# node_v2.net
KiCad netlist of a schematic drawn in EAGLE
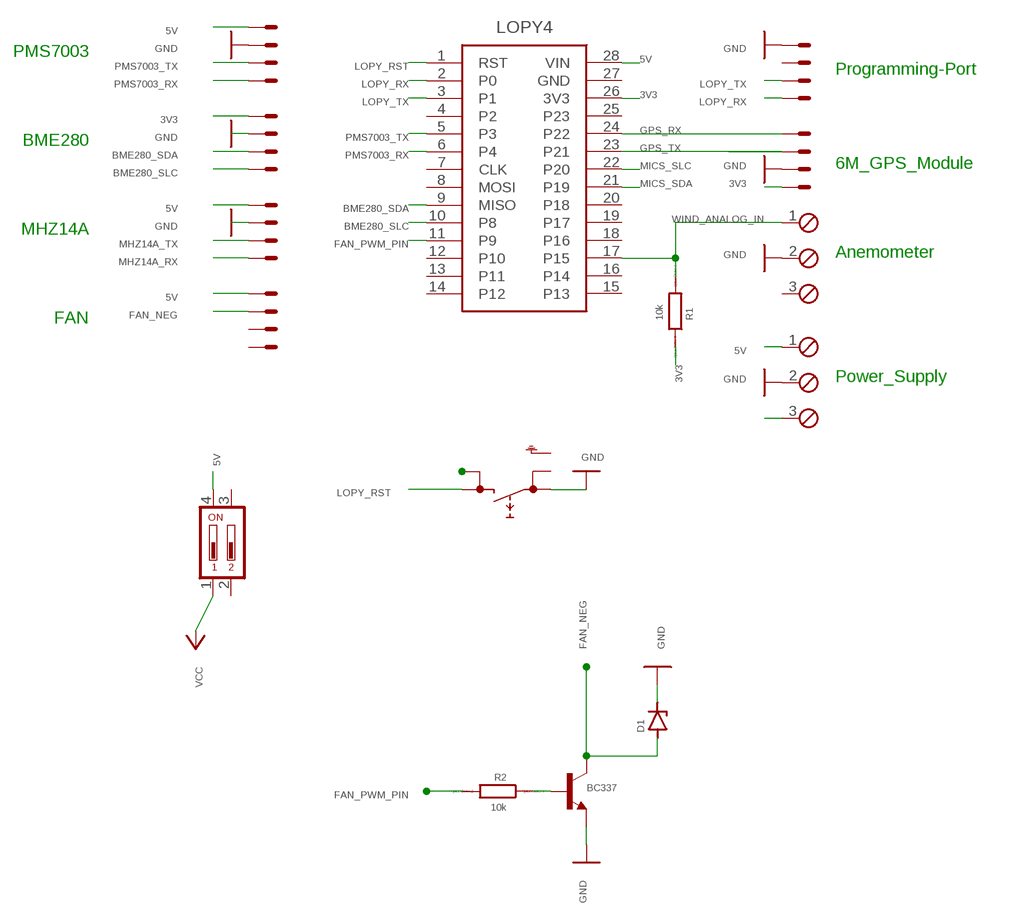
[diagram p0: schematic, sheet 1]

(export (version "E")
  (design (tool "Eeschema 10.0.6"))
  (components
    (comp (ref "D1")
      (value "1N821")
      (footprint "eagle-import:DO35Z10")
      (libsource (lib "eagle-import") (part "1N821"))
    )
    (comp (ref "IC1")
      (value "LOPY4")
      (footprint "eagle-import:LOPY4")
      (fields (field (name "MOUSER_PART_NUMBER") "365-LOPY4"))
      (libsource (lib "eagle-import") (part "LOPY4"))
    )
    (comp (ref "R1")
      (value "10k")
      (footprint "eagle-import:0207_10")
      (fields (field (name "SPICEMODEL") "12"))
      (libsource (lib "eagle-import") (part "R0207/10"))
    )
    (comp (ref "R2")
      (value "10k")
      (footprint "eagle-import:0207_10")
      (fields (field (name "SPICEMODEL") "12"))
      (libsource (lib "eagle-import") (part "R0207/10"))
    )
    (comp (ref "S1")
      (value "DA02")
      (footprint "eagle-import:DA-02")
      (libsource (lib "eagle-import") (part "DA02"))
    )
    (comp (ref "S2")
      (value "SKHMPSE010")
      (footprint "eagle-import:SKHMPXE010")
      (libsource (lib "eagle-import") (part "SKHMPE010S"))
    )
    (comp (ref "T1")
      (value "BC337")
      (footprint "eagle-import:TO92")
      (libsource (lib "eagle-import") (part "BC337"))
    )
    (comp (ref "X1")
      (value "22-23-2041")
      (footprint "eagle-import:22-23-2041")
      (fields (field (name "MF") "MOLEX"))
      (libsource (lib "eagle-import") (part "22-23-2041"))
    )
    (comp (ref "X4")
      (value "22-23-2041")
      (footprint "eagle-import:22-23-2041")
      (fields (field (name "MF") "MOLEX"))
      (libsource (lib "eagle-import") (part "22-23-2041"))
    )
    (comp (ref "X5")
      (value "MPT3")
      (footprint "eagle-import:3POL254")
      (libsource (lib "eagle-import") (part "MPT3"))
    )
    (comp (ref "X6")
      (value "MPT3")
      (footprint "eagle-import:3POL254")
      (libsource (lib "eagle-import") (part "MPT3"))
    )
    (comp (ref "X7")
      (value "22-23-2041")
      (footprint "eagle-import:22-23-2041")
      (fields (field (name "MF") "MOLEX"))
      (libsource (lib "eagle-import") (part "22-23-2041"))
    )
    (comp (ref "X8")
      (value "22-23-2041")
      (footprint "eagle-import:22-23-2041")
      (fields (field (name "MF") "MOLEX"))
      (libsource (lib "eagle-import") (part "22-23-2041"))
    )
    (comp (ref "X9")
      (value "22-23-2041")
      (footprint "eagle-import:22-23-2041")
      (fields (field (name "MF") "MOLEX"))
      (libsource (lib "eagle-import") (part "22-23-2041"))
    )
    (comp (ref "X10")
      (value "22-23-2041")
      (footprint "eagle-import:22-23-2041")
      (fields (field (name "MF") "MOLEX"))
      (libsource (lib "eagle-import") (part "22-23-2041"))
    )
  )
  (nets
    (net (code "1") (name "/3V3") (class "Default")
      (node (ref "IC1") (pin "26") (pinfunction "3V3_26") (pintype "bidirectional"))
      (node (ref "R1") (pin "1") (pinfunction "1_1") (pintype "passive"))
      (node (ref "X4") (pin "4") (pinfunction "S_4") (pintype "passive"))
      (node (ref "X8") (pin "1") (pinfunction "S_1") (pintype "passive"))
    )
    (net (code "2") (name "/5V") (class "Default")
      (node (ref "IC1") (pin "28") (pinfunction "VIN_28") (pintype "bidirectional"))
      (node (ref "S1") (pin "4") (pinfunction "4_4") (pintype "passive"))
      (node (ref "X10") (pin "1") (pinfunction "S_1") (pintype "passive"))
      (node (ref "X6") (pin "1") (pinfunction "1_1") (pintype "passive"))
      (node (ref "X7") (pin "1") (pinfunction "S_1") (pintype "passive"))
      (node (ref "X9") (pin "1") (pinfunction "S_1") (pintype "passive"))
    )
    (net (code "3") (name "/BME280_SDA") (class "Default")
      (node (ref "IC1") (pin "9") (pinfunction "MISO_9") (pintype "bidirectional"))
      (node (ref "X8") (pin "3") (pinfunction "S_3") (pintype "passive"))
    )
    (net (code "4") (name "/BME280_SLC") (class "Default")
      (node (ref "IC1") (pin "10") (pinfunction "P8_10") (pintype "bidirectional"))
      (node (ref "X8") (pin "4") (pinfunction "S_4") (pintype "passive"))
    )
    (net (code "5") (name "/FAN_NEG") (class "Default")
      (node (ref "D1") (pin "A") (pinfunction "A_A") (pintype "passive"))
      (node (ref "T1") (pin "3") (pinfunction "C_3") (pintype "passive"))
      (node (ref "X10") (pin "2") (pinfunction "S_2") (pintype "passive"))
    )
    (net (code "6") (name "/FAN_PWM_PIN") (class "Default")
      (node (ref "IC1") (pin "11") (pinfunction "P9_11") (pintype "bidirectional"))
      (node (ref "R2") (pin "2") (pinfunction "2_2") (pintype "passive"))
    )
    (net (code "7") (name "/GPS_RX") (class "Default")
      (node (ref "IC1") (pin "24") (pinfunction "P22_24") (pintype "bidirectional"))
      (node (ref "X4") (pin "1") (pinfunction "S_1") (pintype "passive"))
    )
    (net (code "8") (name "/GPS_TX") (class "Default")
      (node (ref "IC1") (pin "23") (pinfunction "P21_23") (pintype "bidirectional"))
      (node (ref "X4") (pin "2") (pinfunction "S_2") (pintype "passive"))
    )
    (net (code "9") (name "/LOPY_RST") (class "Default")
      (node (ref "IC1") (pin "1") (pinfunction "RST_1") (pintype "bidirectional"))
      (node (ref "S2") (pin "3") (pinfunction "2.1_3") (pintype "passive"))
    )
    (net (code "10") (name "/LOPY_RX") (class "Default")
      (node (ref "IC1") (pin "2") (pinfunction "P0_2") (pintype "bidirectional"))
    )
    (net (code "11") (name "/LOPY_TX") (class "Default")
      (node (ref "IC1") (pin "3") (pinfunction "P1_3") (pintype "bidirectional"))
    )
    (net (code "12") (name "/MHZ14A_RX") (class "Default")
      (node (ref "X9") (pin "4") (pinfunction "S_4") (pintype "passive"))
    )
    (net (code "13") (name "/MHZ14A_TX") (class "Default")
      (node (ref "X9") (pin "3") (pinfunction "S_3") (pintype "passive"))
    )
    (net (code "14") (name "/MICS_SDA") (class "Default")
      (node (ref "IC1") (pin "21") (pinfunction "P19_21") (pintype "bidirectional"))
    )
    (net (code "15") (name "/MICS_SLC") (class "Default")
      (node (ref "IC1") (pin "22") (pinfunction "P20_22") (pintype "bidirectional"))
    )
    (net (code "16") (name "/PMS7003_RX") (class "Default")
      (node (ref "IC1") (pin "6") (pinfunction "P4_6") (pintype "bidirectional"))
      (node (ref "X7") (pin "4") (pinfunction "S_4") (pintype "passive"))
    )
    (net (code "17") (name "/PMS7003_TX") (class "Default")
      (node (ref "IC1") (pin "5") (pinfunction "P3_5") (pintype "bidirectional"))
      (node (ref "X7") (pin "3") (pinfunction "S_3") (pintype "passive"))
    )
    (net (code "18") (name "/WIND_ANALOG_IN") (class "Default")
      (node (ref "IC1") (pin "17") (pinfunction "P15_17") (pintype "bidirectional"))
      (node (ref "R1") (pin "2") (pinfunction "2_2") (pintype "passive"))
      (node (ref "X5") (pin "1") (pinfunction "1_1") (pintype "passive"))
    )
    (net (code "19") (name "GND") (class "Default")
      (node (ref "D1") (pin "C") (pinfunction "C_C") (pintype "passive"))
      (node (ref "S2") (pin "1") (pinfunction "1.1_1") (pintype "passive"))
      (node (ref "T1") (pin "1") (pinfunction "E_1") (pintype "passive"))
      (node (ref "X1") (pin "1") (pinfunction "S_1") (pintype "passive"))
      (node (ref "X4") (pin "3") (pinfunction "S_3") (pintype "passive"))
      (node (ref "X5") (pin "2") (pinfunction "1_2") (pintype "passive"))
      (node (ref "X6") (pin "2") (pinfunction "1_2") (pintype "passive"))
      (node (ref "X7") (pin "2") (pinfunction "S_2") (pintype "passive"))
      (node (ref "X8") (pin "2") (pinfunction "S_2") (pintype "passive"))
      (node (ref "X9") (pin "2") (pinfunction "S_2") (pintype "passive"))
    )
    (net (code "20") (name "Net-(T1-B)") (class "Default")
      (node (ref "R2") (pin "1") (pinfunction "1_1") (pintype "passive"))
      (node (ref "T1") (pin "2") (pinfunction "B_2") (pintype "passive"))
    )
    (net (code "21") (name "VCC") (class "Default")
      (node (ref "S1") (pin "1") (pinfunction "1_1") (pintype "passive"))
    )
    (net (code "22") (name "unconnected-(IC1-CLK-Pad7)") (class "Default")
      (node (ref "IC1") (pin "7") (pinfunction "CLK_7") (pintype "bidirectional"))
    )
    (net (code "23") (name "unconnected-(IC1-GND-Pad27)") (class "Default")
      (node (ref "IC1") (pin "27") (pinfunction "GND_27") (pintype "bidirectional"))
    )
    (net (code "24") (name "unconnected-(IC1-MOSI-Pad8)") (class "Default")
      (node (ref "IC1") (pin "8") (pinfunction "MOSI_8") (pintype "bidirectional"))
    )
    (net (code "25") (name "unconnected-(IC1-P2-Pad4)") (class "Default")
      (node (ref "IC1") (pin "4") (pinfunction "P2_4") (pintype "bidirectional"))
    )
    (net (code "26") (name "unconnected-(IC1-P10-Pad12)") (class "Default")
      (node (ref "IC1") (pin "12") (pinfunction "P10_12") (pintype "bidirectional"))
    )
    (net (code "27") (name "unconnected-(IC1-P11-Pad13)") (class "Default")
      (node (ref "IC1") (pin "13") (pinfunction "P11_13") (pintype "bidirectional"))
    )
    (net (code "28") (name "unconnected-(IC1-P12-Pad14)") (class "Default")
      (node (ref "IC1") (pin "14") (pinfunction "P12_14") (pintype "bidirectional"))
    )
    (net (code "29") (name "unconnected-(IC1-P13-Pad15)") (class "Default")
      (node (ref "IC1") (pin "15") (pinfunction "P13_15") (pintype "bidirectional"))
    )
    (net (code "30") (name "unconnected-(IC1-P14-Pad16)") (class "Default")
      (node (ref "IC1") (pin "16") (pinfunction "P14_16") (pintype "bidirectional"))
    )
    (net (code "31") (name "unconnected-(IC1-P16-Pad18)") (class "Default")
      (node (ref "IC1") (pin "18") (pinfunction "P16_18") (pintype "bidirectional"))
    )
    (net (code "32") (name "unconnected-(IC1-P17-Pad19)") (class "Default")
      (node (ref "IC1") (pin "19") (pinfunction "P17_19") (pintype "bidirectional"))
    )
    (net (code "33") (name "unconnected-(IC1-P18-Pad20)") (class "Default")
      (node (ref "IC1") (pin "20") (pinfunction "P18_20") (pintype "bidirectional"))
    )
    (net (code "34") (name "unconnected-(IC1-P23-Pad25)") (class "Default")
      (node (ref "IC1") (pin "25") (pinfunction "P23_25") (pintype "bidirectional"))
    )
    (net (code "35") (name "unconnected-(S1-Pad2)") (class "Default")
      (node (ref "S1") (pin "2") (pinfunction "2_2") (pintype "passive"))
    )
    (net (code "36") (name "unconnected-(S1-Pad3)") (class "Default")
      (node (ref "S1") (pin "3") (pinfunction "3_3") (pintype "passive"))
    )
    (net (code "37") (name "unconnected-(S2-1.2-Pad2)") (class "Default")
      (node (ref "S2") (pin "2") (pinfunction "1.2_2") (pintype "passive"))
    )
    (net (code "38") (name "unconnected-(S2-2.2-Pad4)") (class "Default")
      (node (ref "S2") (pin "4") (pinfunction "2.2_4") (pintype "passive"))
    )
    (net (code "39") (name "unconnected-(S2-SH-Pad5)") (class "Default")
      (node (ref "S2") (pin "5") (pinfunction "SH_5") (pintype "passive"))
    )
    (net (code "40") (name "unconnected-(X1B-S-Pad2)") (class "Default")
      (node (ref "X1") (pin "2") (pinfunction "S_2") (pintype "passive"))
    )
    (net (code "41") (name "unconnected-(X1C-S-Pad3)") (class "Default")
      (node (ref "X1") (pin "3") (pinfunction "S_3") (pintype "passive"))
    )
    (net (code "42") (name "unconnected-(X1D-S-Pad4)") (class "Default")
      (node (ref "X1") (pin "4") (pinfunction "S_4") (pintype "passive"))
    )
    (net (code "43") (name "unconnected-(X5C-1-Pad3)") (class "Default")
      (node (ref "X5") (pin "3") (pinfunction "1_3") (pintype "passive"))
    )
    (net (code "44") (name "unconnected-(X6C-1-Pad3)") (class "Default")
      (node (ref "X6") (pin "3") (pinfunction "1_3") (pintype "passive"))
    )
    (net (code "45") (name "unconnected-(X10C-S-Pad3)") (class "Default")
      (node (ref "X10") (pin "3") (pinfunction "S_3") (pintype "passive"))
    )
    (net (code "46") (name "unconnected-(X10D-S-Pad4)") (class "Default")
      (node (ref "X10") (pin "4") (pinfunction "S_4") (pintype "passive"))
    )
  )
)
